# 08_POWER.net
KiCad netlist of a schematic drawn in Altium Designer
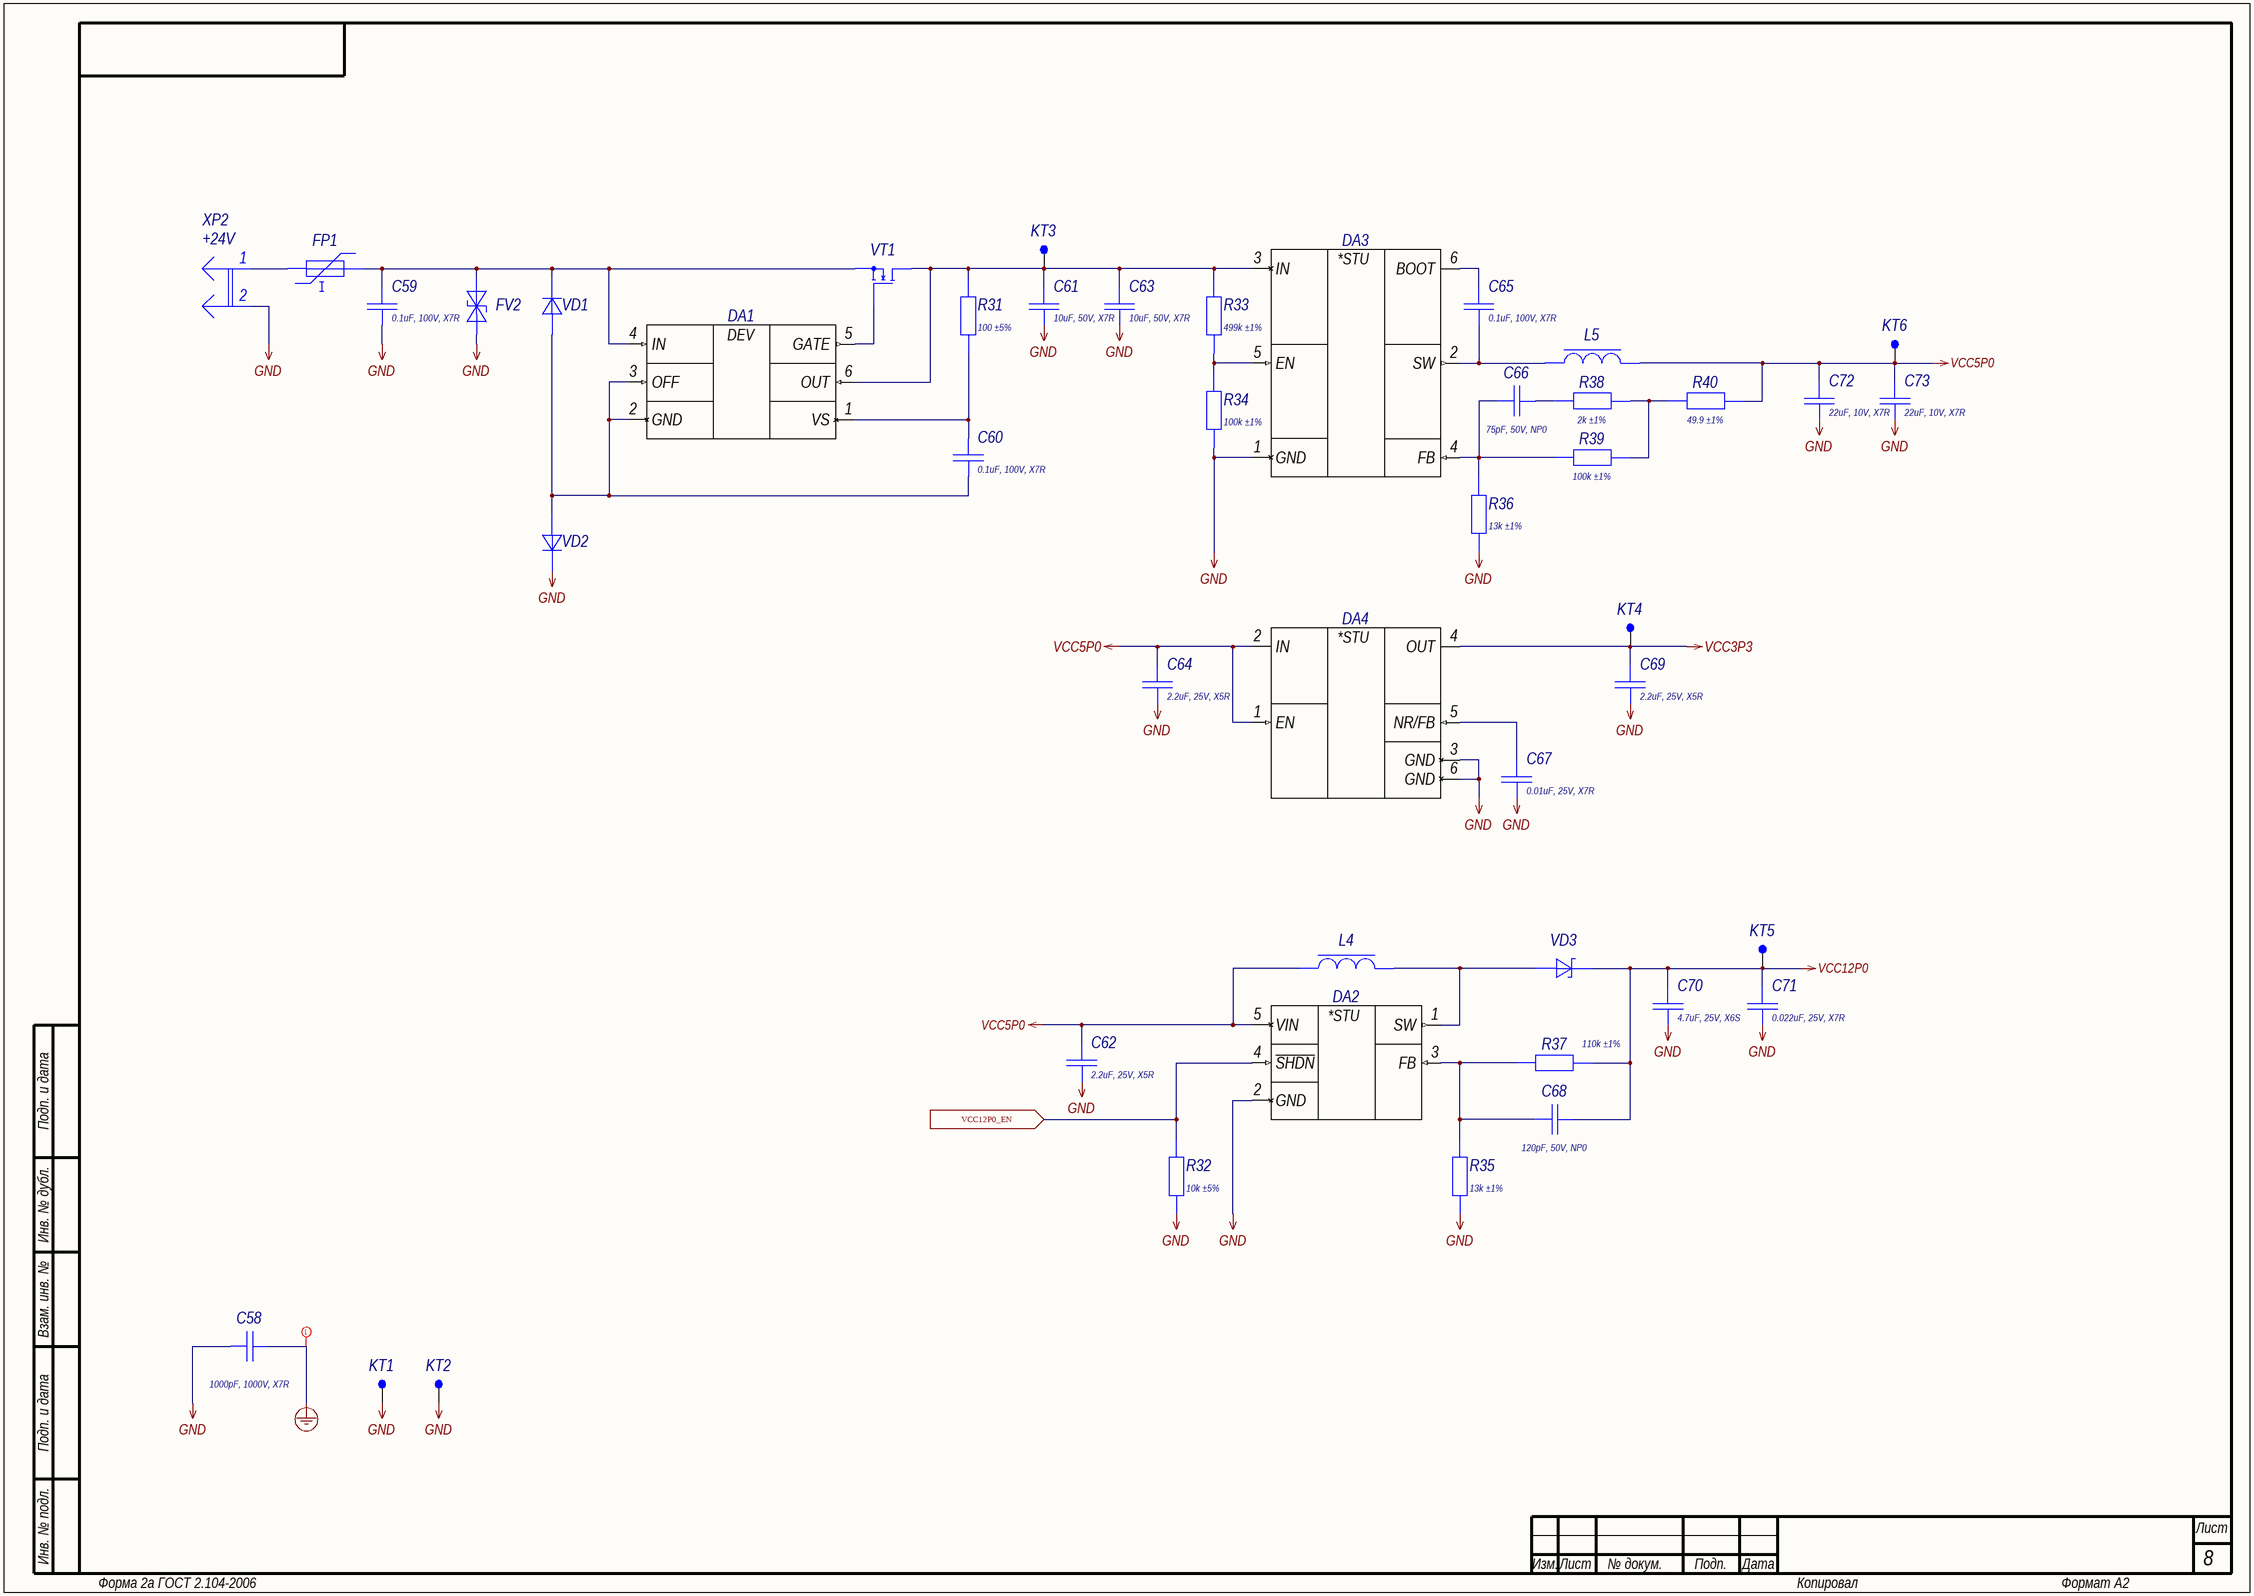
[diagram p0: 08_POWER.SchDoc]

(export (version "E")
  (design (tool "Eeschema 10.0.6"))
  (components
    (comp (ref "C58")
      (value "Capacitor")
      (footprint "C1206")
      (fields
        (field (name "PART NUMBER") "GRM31BR73A102KW01L")
        (field (name "VOLTAGE") "1000V")
        (field (name "TOLERANCE") "±10%")
        (field (name "SCHEMATIC VALUE") "1000pF, 1000V, X7R")
        (field (name "PUBLISHER") "Andrew Danich")
      )
      (libsource (lib "ADLib") (part "Capacitor"))
    )
    (comp (ref "C59")
      (value "Capacitor")
      (footprint "C0603_L")
      (fields
        (field (name "SCHEMATIC VALUE") "0.1uF, 100V, X7R")
        (field (name "PART NUMBER") "GRM188R72A104KA35D")
        (field (name "VOLTAGE") "100V")
        (field (name "TOLERANCE") "±10%")
        (field (name "PUBLISHER") "Andrew Danich")
      )
      (libsource (lib "ADLib") (part "Capacitor"))
    )
    (comp (ref "C60")
      (value "Capacitor")
      (footprint "C0603_L")
      (fields
        (field (name "SCHEMATIC VALUE") "0.1uF, 100V, X7R")
        (field (name "PART NUMBER") "GRM188R72A104KA35D")
        (field (name "VOLTAGE") "100V")
        (field (name "TOLERANCE") "±10%")
        (field (name "PUBLISHER") "Andrew Danich")
      )
      (libsource (lib "ADLib") (part "Capacitor"))
    )
    (comp (ref "C61")
      (value "Capacitor")
      (footprint "C1210_L")
      (fields
        (field (name "SCHEMATIC VALUE") "10uF, 50V, X7R")
        (field (name "PART NUMBER") "GRM32ER71H106KA12L")
        (field (name "VOLTAGE") "50V")
        (field (name "TOLERANCE") "±10%")
        (field (name "PUBLISHER") "Andrew Danich")
      )
      (libsource (lib "ADLib") (part "Capacitor"))
    )
    (comp (ref "C62")
      (value "Capacitor")
      (footprint "C0603_L")
      (fields
        (field (name "SCHEMATIC VALUE") "2.2uF, 25V, X5R")
        (field (name "PART NUMBER") "GRM188R61E225MA12D")
        (field (name "VOLTAGE") "25V")
        (field (name "TOLERANCE") "±20%")
        (field (name "PUBLISHER") "Andrew Danich")
      )
      (libsource (lib "ADLib") (part "Capacitor"))
    )
    (comp (ref "C63")
      (value "Capacitor")
      (footprint "C1210_L")
      (fields
        (field (name "SCHEMATIC VALUE") "10uF, 50V, X7R")
        (field (name "PART NUMBER") "GRM32ER71H106KA12L")
        (field (name "VOLTAGE") "50V")
        (field (name "TOLERANCE") "±10%")
        (field (name "PUBLISHER") "Andrew Danich")
      )
      (libsource (lib "ADLib") (part "Capacitor"))
    )
    (comp (ref "C64")
      (value "Capacitor")
      (footprint "C0603_L")
      (fields
        (field (name "SCHEMATIC VALUE") "2.2uF, 25V, X5R")
        (field (name "PART NUMBER") "GRM188R61E225MA12D")
        (field (name "VOLTAGE") "25V")
        (field (name "TOLERANCE") "±20%")
        (field (name "PUBLISHER") "Andrew Danich")
      )
      (libsource (lib "ADLib") (part "Capacitor"))
    )
    (comp (ref "C65")
      (value "Capacitor")
      (footprint "C0603_L")
      (fields
        (field (name "SCHEMATIC VALUE") "0.1uF, 100V, X7R")
        (field (name "PART NUMBER") "GRM188R72A104KA35D")
        (field (name "VOLTAGE") "100V")
        (field (name "TOLERANCE") "±10%")
        (field (name "PUBLISHER") "Andrew Danich")
      )
      (libsource (lib "ADLib") (part "Capacitor"))
    )
    (comp (ref "C66")
      (value "Capacitor")
      (footprint "C0402_L")
      (fields
        (field (name "SCHEMATIC VALUE") "75pF, 50V, NP0")
        (field (name "PART NUMBER") "GCM1555C1H750JA16D")
        (field (name "VOLTAGE") "50V")
        (field (name "TOLERANCE") "±5%")
        (field (name "PUBLISHER") "Andrew Danich")
      )
      (libsource (lib "ADLib") (part "Capacitor"))
    )
    (comp (ref "C67")
      (value "Capacitor")
      (footprint "C0402_L")
      (fields
        (field (name "SCHEMATIC VALUE") "0.01uF, 25V, X7R")
        (field (name "PART NUMBER") "GCM155R71E103KA37D")
        (field (name "VOLTAGE") "25V")
        (field (name "TOLERANCE") "±10%")
        (field (name "PUBLISHER") "Andrew Danich")
      )
      (libsource (lib "ADLib") (part "Capacitor"))
    )
    (comp (ref "C68")
      (value "Capacitor")
      (footprint "C0402_L")
      (fields
        (field (name "SCHEMATIC VALUE") "120pF, 50V, NP0")
        (field (name "PART NUMBER") "GRM1555C1H121JA01D")
        (field (name "VOLTAGE") "50V")
        (field (name "TOLERANCE") "±5%")
        (field (name "PUBLISHER") "Andrew Danich")
      )
      (libsource (lib "ADLib") (part "Capacitor"))
    )
    (comp (ref "C69")
      (value "Capacitor")
      (footprint "C0603_L")
      (fields
        (field (name "SCHEMATIC VALUE") "2.2uF, 25V, X5R")
        (field (name "PART NUMBER") "GRM188R61E225MA12D")
        (field (name "VOLTAGE") "25V")
        (field (name "TOLERANCE") "±20%")
        (field (name "PUBLISHER") "Andrew Danich")
      )
      (libsource (lib "ADLib") (part "Capacitor"))
    )
    (comp (ref "C70")
      (value "Capacitor")
      (footprint "C0603_L")
      (fields
        (field (name "SCHEMATIC VALUE") "4.7uF, 25V, X6S")
        (field (name "PART NUMBER") "GRM188C81E475KE11D")
        (field (name "VOLTAGE") "25V")
        (field (name "TOLERANCE") "±10%")
        (field (name "PUBLISHER") "Andrew Danich")
      )
      (libsource (lib "ADLib") (part "Capacitor"))
    )
    (comp (ref "C71")
      (value "Capacitor")
      (footprint "C0402_L")
      (fields
        (field (name "SCHEMATIC VALUE") "0.022uF, 25V, X7R")
        (field (name "PART NUMBER") "GCM155R71E223KA55D")
        (field (name "VOLTAGE") "25V")
        (field (name "TOLERANCE") "±10%")
        (field (name "PUBLISHER") "Andrew Danich")
      )
      (libsource (lib "ADLib") (part "Capacitor"))
    )
    (comp (ref "C72")
      (value "Capacitor")
      (footprint "C1206_L")
      (fields
        (field (name "SCHEMATIC VALUE") "22uF, 10V, X7R")
        (field (name "PART NUMBER") "GRM31CR71A226KE15L")
        (field (name "VOLTAGE") "10V")
        (field (name "TOLERANCE") "±10%")
        (field (name "PUBLISHER") "Andrew Danich")
      )
      (libsource (lib "ADLib") (part "Capacitor"))
    )
    (comp (ref "C73")
      (value "Capacitor")
      (footprint "C1206_L")
      (fields
        (field (name "SCHEMATIC VALUE") "22uF, 10V, X7R")
        (field (name "PART NUMBER") "GRM31CR71A226KE15L")
        (field (name "VOLTAGE") "10V")
        (field (name "TOLERANCE") "±10%")
        (field (name "PUBLISHER") "Andrew Danich")
      )
      (libsource (lib "ADLib") (part "Capacitor"))
    )
    (comp (ref "DA1")
      (value "LM5050-1")
      (footprint "SOT-23-6_095P290X160X145_N")
      (fields
        (field (name "PART NUMBER") "LM5050MK-1/NOPB")
        (field (name "MANUFACTURER") "Texas Instruments")
        (field (name "PUBLISHER") "Andrew Danich")
      )
      (libsource (lib "ADLib") (part "LM5050-1"))
    )
    (comp (ref "DA2")
      (value "LMR64010XMF")
      (footprint "SOT-23-5_095P290X160X145_N")
      (fields
        (field (name "PART NUMBER") "LMR64010XMFX/NOPB")
        (field (name "MANUFACTURER") "Texas Instruments")
        (field (name "PUBLISHER") "Andrew Danich")
      )
      (libsource (lib "ADLib") (part "LMR64010XMF"))
    )
    (comp (ref "DA3")
      (value "TPS54308")
      (footprint "SOT-23-6_095P290X160X145_N")
      (fields
        (field (name "PART NUMBER") "TPS54308DDCR")
        (field (name "MANUFACTURER") "Texas Instruments")
        (field (name "PUBLISHER") "Andrew Danich")
      )
      (libsource (lib "ADLib") (part "TPS54308"))
    )
    (comp (ref "DA4")
      (value "TPS786xxDCQ-Series")
      (footprint "SOT-223-6_127P650X350X180_N")
      (fields
        (field (name "PART NUMBER") "TPS78633DCQR")
        (field (name "MANUFACTURER") "Texas Instruments")
        (field (name "PUBLISHER") "Andrew Danich")
      )
      (libsource (lib "ADLib") (part "TPS786xxDCQ-Series"))
    )
    (comp (ref "FP1")
      (value "Fuse_PTC")
      (footprint "F1812_L_H085")
      (fields (field (name "PART NUMBER") "MF-MSMF050/40X-2") (field (name "MANUFACTURER") "Bourns"))
      (libsource (lib "ADLib") (part "Fuse_PTC"))
    )
    (comp (ref "FV2")
      (value "Suppressor-Bi")
      (footprint "SOD-123FL")
      (fields
        (field (name "PART NUMBER") "SMF4L36CA")
        (field (name "MANUFACTURER") "LittleFuse")
        (field (name "PUBLISHER") "Andrew Danich")
      )
      (libsource (lib "ADLib") (part "Suppressor-Bi"))
    )
    (comp (ref "KT1")
      (value "GND")
      (footprint "TP-SMT-R-0.8mm")
      (fields (field (name "PART NUMBER") "TestPoint-SMT-GND") (field (name "PUBLISHER") "Andrew Danich"))
      (libsource (lib "ADLib") (part "TP-S-1"))
    )
    (comp (ref "KT2")
      (value "GND")
      (footprint "TP-SMT-R-0.8mm")
      (fields (field (name "PART NUMBER") "TestPoint-SMT-GND") (field (name "PUBLISHER") "Andrew Danich"))
      (libsource (lib "ADLib") (part "TP-S-1"))
    )
    (comp (ref "KT3")
      (value "VCCIN")
      (footprint "TP-SMT-C-0.5mm")
      (fields (field (name "PART NUMBER") "TestPoint-SMT") (field (name "PUBLISHER") "Andrew Danich"))
      (libsource (lib "ADLib") (part "TP-S-1"))
    )
    (comp (ref "KT4")
      (value "3.3V")
      (footprint "TP-SMT-C-0.5mm")
      (fields (field (name "PART NUMBER") "TestPoint-SMT") (field (name "PUBLISHER") "Andrew Danich"))
      (libsource (lib "ADLib") (part "TP-S-1"))
    )
    (comp (ref "KT5")
      (value "12.0V")
      (footprint "TP-SMT-C-0.5mm")
      (fields (field (name "PART NUMBER") "TestPoint-SMT") (field (name "PUBLISHER") "Andrew Danich"))
      (libsource (lib "ADLib") (part "TP-S-1"))
    )
    (comp (ref "KT6")
      (value "5.0V")
      (footprint "TP-SMT-C-0.5mm")
      (fields (field (name "PART NUMBER") "TestPoint-SMT") (field (name "PUBLISHER") "Andrew Danich"))
      (libsource (lib "ADLib") (part "TP-S-1"))
    )
    (comp (ref "L4")
      (value "Coil")
      (footprint "SRP3020TA-Series")
      (fields
        (field (name "PART NUMBER") "SRP3020TA-4R7M")
        (field (name "TOLERANCE") "±20%")
        (field (name "MANUFACTURER") "Bourns")
        (field (name "PUBLISHER") "Andrew Danich")
      )
      (libsource (lib "ADLib") (part "Coil"))
    )
    (comp (ref "L5")
      (value "Coil")
      (footprint "SRP7028C-Series")
      (fields
        (field (name "PART NUMBER") "SRP7028C-150M")
        (field (name "TOLERANCE") "±20%")
        (field (name "MANUFACTURER") "Bourns")
        (field (name "PUBLISHER") "Andrew Danich")
      )
      (libsource (lib "ADLib") (part "Coil"))
    )
    (comp (ref "R31")
      (value "Resistor")
      (footprint "R0603_L")
      (fields
        (field (name "SCHEMATIC VALUE") "100 ±5%")
        (field (name "PART NUMBER") "RC0603JR-07100R")
        (field (name "TOLERANCE") "±5%")
        (field (name "MANUFACTURER") "Yageo")
        (field (name "PUBLISHER") "Andrew Danich")
      )
      (libsource (lib "ADLib") (part "Resistor"))
    )
    (comp (ref "R32")
      (value "Resistor")
      (footprint "R0402_L")
      (fields
        (field (name "SCHEMATIC VALUE") "10k ±5%")
        (field (name "PART NUMBER") "RC0402JR-0710KL")
        (field (name "TOLERANCE") "±5%")
        (field (name "MANUFACTURER") "Yageo")
        (field (name "PUBLISHER") "Andrew Danich")
      )
      (libsource (lib "ADLib") (part "Resistor"))
    )
    (comp (ref "R33")
      (value "Resistor")
      (footprint "R0402_L")
      (fields
        (field (name "SCHEMATIC VALUE") "499k ±1%")
        (field (name "PART NUMBER") "RC0402FR-07499KL")
        (field (name "TOLERANCE") "±1%")
        (field (name "MANUFACTURER") "Yageo")
        (field (name "PUBLISHER") "Andrew Danich")
      )
      (libsource (lib "ADLib") (part "Resistor"))
    )
    (comp (ref "R34")
      (value "Resistor")
      (footprint "R0402_L")
      (fields
        (field (name "SCHEMATIC VALUE") "100k ±1%")
        (field (name "PART NUMBER") "RC0402FR-07100KL")
        (field (name "TOLERANCE") "±1%")
        (field (name "MANUFACTURER") "Yageo")
        (field (name "PUBLISHER") "Andrew Danich")
      )
      (libsource (lib "ADLib") (part "Resistor"))
    )
    (comp (ref "R35")
      (value "Resistor")
      (footprint "R0402_L")
      (fields
        (field (name "SCHEMATIC VALUE") "13k ±1%")
        (field (name "PART NUMBER") "RC0402FR-0713KL")
        (field (name "TOLERANCE") "±1%")
        (field (name "MANUFACTURER") "Yageo")
        (field (name "PUBLISHER") "Andrew Danich")
      )
      (libsource (lib "ADLib") (part "Resistor"))
    )
    (comp (ref "R36")
      (value "Resistor")
      (footprint "R0402_L")
      (fields
        (field (name "SCHEMATIC VALUE") "13k ±1%")
        (field (name "PART NUMBER") "RC0402FR-0713KL")
        (field (name "TOLERANCE") "±1%")
        (field (name "MANUFACTURER") "Yageo")
        (field (name "PUBLISHER") "Andrew Danich")
      )
      (libsource (lib "ADLib") (part "Resistor"))
    )
    (comp (ref "R37")
      (value "Resistor")
      (footprint "R0402_L")
      (fields
        (field (name "SCHEMATIC VALUE") "110k ±1%")
        (field (name "PART NUMBER") "RC0402FR-07110KL")
        (field (name "TOLERANCE") "±1%")
        (field (name "MANUFACTURER") "Yageo")
        (field (name "PUBLISHER") "Andrew Danich")
      )
      (libsource (lib "ADLib") (part "Resistor"))
    )
    (comp (ref "R38")
      (value "Resistor")
      (footprint "R0402_L")
      (fields
        (field (name "SCHEMATIC VALUE") "2k ±1%")
        (field (name "PART NUMBER") "RC0402FR-072KL")
        (field (name "TOLERANCE") "±1%")
        (field (name "MANUFACTURER") "Yageo")
        (field (name "PUBLISHER") "Andrew Danich")
      )
      (libsource (lib "ADLib") (part "Resistor"))
    )
    (comp (ref "R39")
      (value "Resistor")
      (footprint "R0402_L")
      (fields
        (field (name "SCHEMATIC VALUE") "100k ±1%")
        (field (name "PART NUMBER") "RC0402FR-07100KL")
        (field (name "TOLERANCE") "±1%")
        (field (name "MANUFACTURER") "Yageo")
        (field (name "PUBLISHER") "Andrew Danich")
      )
      (libsource (lib "ADLib") (part "Resistor"))
    )
    (comp (ref "R40")
      (value "Resistor")
      (footprint "R0402_L")
      (fields
        (field (name "SCHEMATIC VALUE") "49.9 ±1%")
        (field (name "PART NUMBER") "RC0402FR-0749R9L")
        (field (name "TOLERANCE") "±1%")
        (field (name "MANUFACTURER") "Yageo")
        (field (name "PUBLISHER") "Andrew Danich")
      )
      (libsource (lib "ADLib") (part "Resistor"))
    )
    (comp (ref "VD1")
      (value "Diode")
      (footprint "SOD-523")
      (fields
        (field (name "PART NUMBER") "1N4148WT-7")
        (field (name "MANUFACTURER") "Diodes Incorporated")
        (field (name "PUBLISHER") "Andrew Danich")
      )
      (libsource (lib "ADLib") (part "Diode"))
    )
    (comp (ref "VD2")
      (value "Diode")
      (footprint "SOD-523")
      (fields
        (field (name "PART NUMBER") "1N4148WT-7")
        (field (name "MANUFACTURER") "Diodes Incorporated")
        (field (name "PUBLISHER") "Andrew Danich")
      )
      (libsource (lib "ADLib") (part "Diode"))
    )
    (comp (ref "VD3")
      (value "Schottky")
      (footprint "SOD-123")
      (fields
        (field (name "PART NUMBER") "MBR0540T1G")
        (field (name "MANUFACTURER") "ON Semiconductor")
        (field (name "PUBLISHER") "Andrew Danich")
      )
      (libsource (lib "ADLib") (part "Schottky"))
    )
    (comp (ref "VT1")
      (value "MOSFET-N_32")
      (footprint "SOT-23_190P290X160X145_N")
      (fields
        (field (name "PART NUMBER") "IRLML0030TRPBF")
        (field (name "MANUFACTURER") "International Rectifier")
        (field (name "PUBLISHER") "Andrew Danich")
      )
      (libsource (lib "ADLib") (part "MOSFET-N_32"))
    )
    (comp (ref "XP2")
      (value "+24V")
      (footprint "1827868")
      (fields
        (field (name "PART NUMBER") "1827868")
        (field (name "MANUFACTURER") "Phoenix Contact")
        (field (name "PUBLISHER") "Andrew Danich")
      )
      (libsource (lib "ADLib") (part "Con-2-M"))
    )
  )
  (nets
    (net (code "1") (name "/VCC12P0_EN") (class "Default")
      (node (ref "DA2") (pin "4") (pinfunction "~{SHDN}_4") (pintype "input"))
      (node (ref "R32") (pin "2") (pinfunction "2_2") (pintype "passive"))
    )
    (net (code "2") (name "EARTH") (class "Default")
      (node (ref "C58") (pin "2") (pinfunction "2_2") (pintype "passive"))
    )
    (net (code "3") (name "GND") (class "Default")
      (node (ref "C58") (pin "1") (pinfunction "1_1") (pintype "passive"))
      (node (ref "C59") (pin "1") (pinfunction "1_1") (pintype "passive"))
      (node (ref "C61") (pin "1") (pinfunction "1_1") (pintype "passive"))
      (node (ref "C62") (pin "1") (pinfunction "1_1") (pintype "passive"))
      (node (ref "C63") (pin "1") (pinfunction "1_1") (pintype "passive"))
      (node (ref "C64") (pin "1") (pinfunction "1_1") (pintype "passive"))
      (node (ref "C67") (pin "1") (pinfunction "1_1") (pintype "passive"))
      (node (ref "C69") (pin "1") (pinfunction "1_1") (pintype "passive"))
      (node (ref "C70") (pin "1") (pinfunction "1_1") (pintype "passive"))
      (node (ref "C71") (pin "1") (pinfunction "1_1") (pintype "passive"))
      (node (ref "C72") (pin "1") (pinfunction "1_1") (pintype "passive"))
      (node (ref "C73") (pin "1") (pinfunction "1_1") (pintype "passive"))
      (node (ref "DA2") (pin "2") (pinfunction "GND_2") (pintype "power_in"))
      (node (ref "DA3") (pin "1") (pinfunction "GND_1") (pintype "power_in"))
      (node (ref "DA4") (pin "3") (pinfunction "GND_3") (pintype "power_in"))
      (node (ref "DA4") (pin "6") (pinfunction "GND_6") (pintype "power_in"))
      (node (ref "FV2") (pin "1") (pinfunction "А_1") (pintype "passive"))
      (node (ref "KT1") (pin "1") (pinfunction "1_1") (pintype "passive"))
      (node (ref "KT2") (pin "1") (pinfunction "1_1") (pintype "passive"))
      (node (ref "R32") (pin "1") (pinfunction "1_1") (pintype "passive"))
      (node (ref "R34") (pin "1") (pinfunction "1_1") (pintype "passive"))
      (node (ref "R35") (pin "1") (pinfunction "1_1") (pintype "passive"))
      (node (ref "R36") (pin "1") (pinfunction "1_1") (pintype "passive"))
      (node (ref "VD2") (pin "2") (pinfunction "К_2") (pintype "passive"))
      (node (ref "XP2") (pin "2") (pintype "passive"))
    )
    (net (code "4") (name "Net-(C66-Pad2)") (class "Default")
      (node (ref "C66") (pin "2") (pinfunction "2_2") (pintype "passive"))
      (node (ref "R38") (pin "1") (pinfunction "1_1") (pintype "passive"))
    )
    (net (code "5") (name "Net-(DA1-GATE)") (class "Default")
      (node (ref "DA1") (pin "5") (pinfunction "GATE_5") (pintype "output"))
      (node (ref "VT1") (pin "1") (pinfunction "G_1") (pintype "passive"))
    )
    (net (code "6") (name "Net-(DA1-GND)") (class "Default")
      (node (ref "C60") (pin "1") (pinfunction "1_1") (pintype "passive"))
      (node (ref "DA1") (pin "2") (pinfunction "GND_2") (pintype "power_in"))
      (node (ref "DA1") (pin "3") (pinfunction "OFF_3") (pintype "input"))
      (node (ref "VD1") (pin "1") (pinfunction "А_1") (pintype "passive"))
      (node (ref "VD2") (pin "1") (pinfunction "А_1") (pintype "passive"))
    )
    (net (code "7") (name "Net-(DA1-IN)") (class "Default")
      (node (ref "C59") (pin "2") (pinfunction "2_2") (pintype "passive"))
      (node (ref "DA1") (pin "4") (pinfunction "IN_4") (pintype "input"))
      (node (ref "FP1") (pin "2") (pinfunction "2_2") (pintype "passive"))
      (node (ref "FV2") (pin "2") (pinfunction "К_2") (pintype "passive"))
      (node (ref "VD1") (pin "2") (pinfunction "К_2") (pintype "passive"))
      (node (ref "VT1") (pin "2") (pinfunction "S_2") (pintype "passive"))
    )
    (net (code "8") (name "Net-(DA1-OUT)") (class "Default")
      (node (ref "C61") (pin "2") (pinfunction "2_2") (pintype "passive"))
      (node (ref "C63") (pin "2") (pinfunction "2_2") (pintype "passive"))
      (node (ref "DA1") (pin "6") (pinfunction "OUT_6") (pintype "input"))
      (node (ref "DA3") (pin "3") (pinfunction "IN_3") (pintype "power_in"))
      (node (ref "KT3") (pin "1") (pinfunction "1_1") (pintype "passive"))
      (node (ref "R31") (pin "2") (pinfunction "2_2") (pintype "passive"))
      (node (ref "R33") (pin "2") (pinfunction "2_2") (pintype "passive"))
      (node (ref "VT1") (pin "3") (pinfunction "D_3") (pintype "passive"))
    )
    (net (code "9") (name "Net-(DA1-VS)") (class "Default")
      (node (ref "C60") (pin "2") (pinfunction "2_2") (pintype "passive"))
      (node (ref "DA1") (pin "1") (pinfunction "VS_1") (pintype "power_in"))
      (node (ref "R31") (pin "1") (pinfunction "1_1") (pintype "passive"))
    )
    (net (code "10") (name "Net-(DA2-FB)") (class "Default")
      (node (ref "C68") (pin "1") (pinfunction "1_1") (pintype "passive"))
      (node (ref "DA2") (pin "3") (pinfunction "FB_3") (pintype "input"))
      (node (ref "R35") (pin "2") (pinfunction "2_2") (pintype "passive"))
      (node (ref "R37") (pin "2") (pinfunction "2_2") (pintype "passive"))
    )
    (net (code "11") (name "Net-(DA2-SW)") (class "Default")
      (node (ref "DA2") (pin "1") (pinfunction "SW_1") (pintype "output"))
      (node (ref "L4") (pin "2") (pinfunction "2_2") (pintype "passive"))
      (node (ref "VD3") (pin "1") (pinfunction "А_1") (pintype "passive"))
    )
    (net (code "12") (name "Net-(DA3-BOOT)") (class "Default")
      (node (ref "C65") (pin "2") (pinfunction "2_2") (pintype "passive"))
      (node (ref "DA3") (pin "6") (pinfunction "BOOT_6") (pintype "passive"))
    )
    (net (code "13") (name "Net-(DA3-EN)") (class "Default")
      (node (ref "DA3") (pin "5") (pinfunction "EN_5") (pintype "input"))
      (node (ref "R33") (pin "1") (pinfunction "1_1") (pintype "passive"))
      (node (ref "R34") (pin "2") (pinfunction "2_2") (pintype "passive"))
    )
    (net (code "14") (name "Net-(DA3-FB)") (class "Default")
      (node (ref "C66") (pin "1") (pinfunction "1_1") (pintype "passive"))
      (node (ref "DA3") (pin "4") (pinfunction "FB_4") (pintype "input"))
      (node (ref "R36") (pin "2") (pinfunction "2_2") (pintype "passive"))
      (node (ref "R39") (pin "1") (pinfunction "1_1") (pintype "passive"))
    )
    (net (code "15") (name "Net-(DA3-SW)") (class "Default")
      (node (ref "C65") (pin "1") (pinfunction "1_1") (pintype "passive"))
      (node (ref "DA3") (pin "2") (pinfunction "SW_2") (pintype "output"))
      (node (ref "L5") (pin "1") (pinfunction "1_1") (pintype "passive"))
    )
    (net (code "16") (name "Net-(DA4-NR{slash}FB)") (class "Default")
      (node (ref "C67") (pin "2") (pinfunction "2_2") (pintype "passive"))
      (node (ref "DA4") (pin "5") (pinfunction "NR/FB_5") (pintype "input"))
    )
    (net (code "17") (name "Net-(FP1-Pad1)") (class "Default")
      (node (ref "FP1") (pin "1") (pinfunction "1_1") (pintype "passive"))
      (node (ref "XP2") (pin "1") (pintype "passive"))
    )
    (net (code "18") (name "Net-(R38-Pad2)") (class "Default")
      (node (ref "R38") (pin "2") (pinfunction "2_2") (pintype "passive"))
      (node (ref "R39") (pin "2") (pinfunction "2_2") (pintype "passive"))
      (node (ref "R40") (pin "1") (pinfunction "1_1") (pintype "passive"))
    )
    (net (code "19") (name "VCC3P3") (class "Default")
      (node (ref "C69") (pin "2") (pinfunction "2_2") (pintype "passive"))
      (node (ref "DA4") (pin "4") (pinfunction "OUT_4") (pintype "power_in"))
      (node (ref "KT4") (pin "1") (pinfunction "1_1") (pintype "passive"))
    )
    (net (code "20") (name "VCC5P0") (class "Default")
      (node (ref "C62") (pin "2") (pinfunction "2_2") (pintype "passive"))
      (node (ref "C64") (pin "2") (pinfunction "2_2") (pintype "passive"))
      (node (ref "C72") (pin "2") (pinfunction "2_2") (pintype "passive"))
      (node (ref "C73") (pin "2") (pinfunction "2_2") (pintype "passive"))
      (node (ref "DA2") (pin "5") (pinfunction "VIN_5") (pintype "power_in"))
      (node (ref "DA4") (pin "1") (pinfunction "EN_1") (pintype "input"))
      (node (ref "DA4") (pin "2") (pinfunction "IN_2") (pintype "power_in"))
      (node (ref "KT6") (pin "1") (pinfunction "1_1") (pintype "passive"))
      (node (ref "L4") (pin "1") (pinfunction "1_1") (pintype "passive"))
      (node (ref "L5") (pin "2") (pinfunction "2_2") (pintype "passive"))
      (node (ref "R40") (pin "2") (pinfunction "2_2") (pintype "passive"))
    )
    (net (code "21") (name "VCC12P0") (class "Default")
      (node (ref "C68") (pin "2") (pinfunction "2_2") (pintype "passive"))
      (node (ref "C70") (pin "2") (pinfunction "2_2") (pintype "passive"))
      (node (ref "C71") (pin "2") (pinfunction "2_2") (pintype "passive"))
      (node (ref "KT5") (pin "1") (pinfunction "1_1") (pintype "passive"))
      (node (ref "R37") (pin "1") (pinfunction "1_1") (pintype "passive"))
      (node (ref "VD3") (pin "2") (pinfunction "К_2") (pintype "passive"))
    )
  )
)
